# Main.net
KiCad netlist of a schematic drawn in Altium Designer
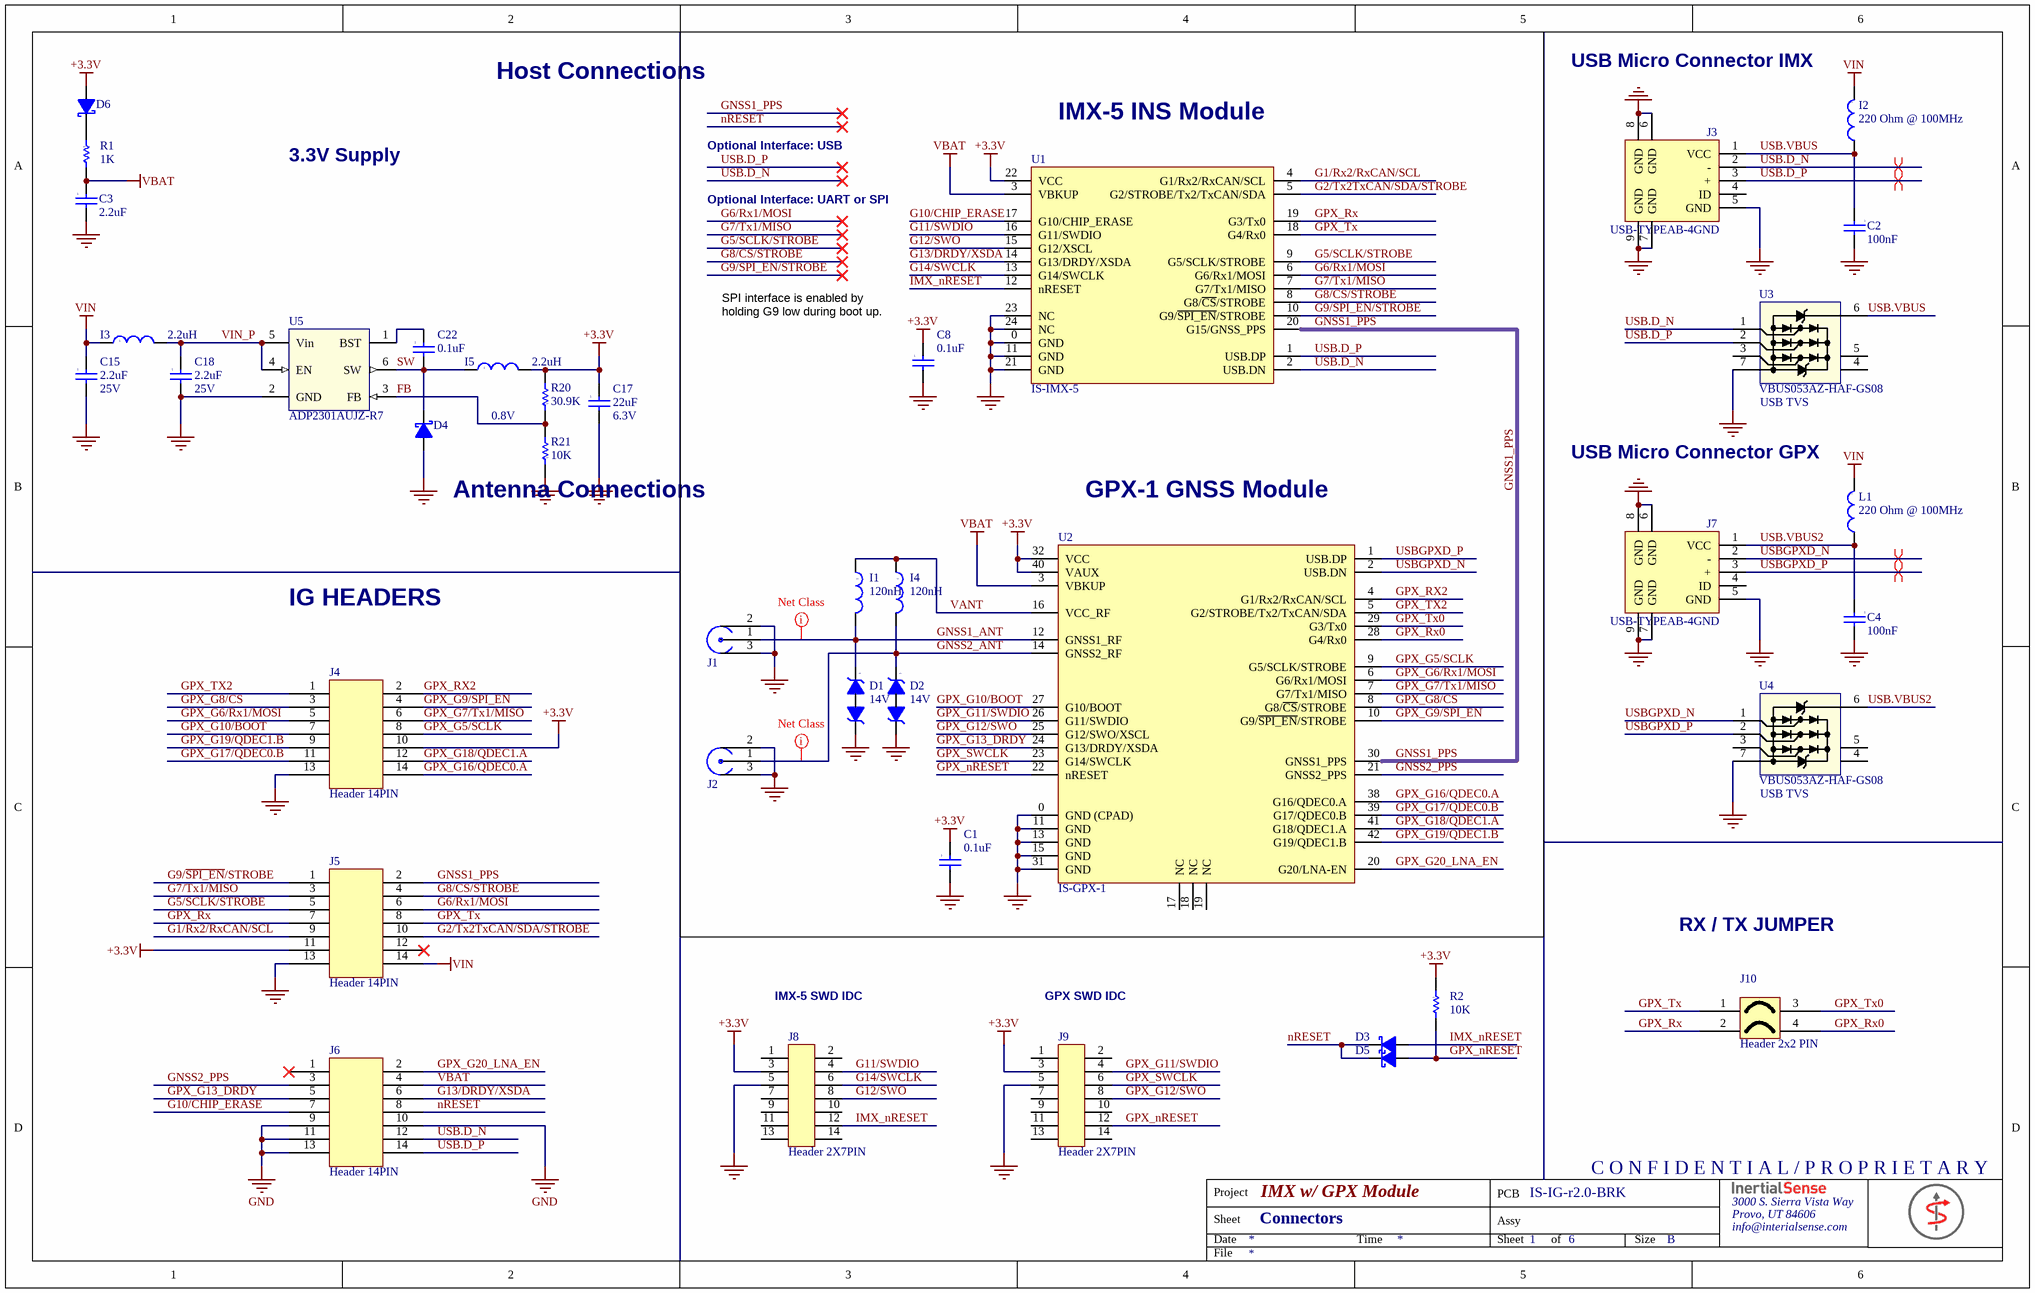
[diagram p0: Main.SchDoc]

(export (version "E")
  (design (tool "Eeschema 10.0.6"))
  (components
    (comp (ref "C1")
      (value "0.1uF")
      (footprint "0402")
      (description "CAP CER .10UF 50V X7R 10% 0402")
      (fields
        (field (name "MANUFACTURER") "TDK Corporation")
        (field (name "MANUFACTURER PART NUMBER") "C1005X7R1H104K")
        (field (name "PUBLISHER") "Altium Limited")
      )
      (libsource (lib "General") (part "Cap"))
    )
    (comp (ref "C2")
      (value "100nF")
      (footprint "0402")
      (description "CAP CER .10UF 50V X7R 10% 0402")
      (fields
        (field (name "MANUFACTURER") "TDK Corporation")
        (field (name "MANUFACTURER PART NUMBER") "C1005X7R1H104K")
        (field (name "PUBLISHER") "Altium Limited")
      )
      (libsource (lib "General") (part "Cap"))
    )
    (comp (ref "C3")
      (value "2.2uF")
      (footprint "0402")
      (description "0402 2.2 uF 6.3 V ±10% Tolerance X6S Multilayer Ceramic Capacitor")
      (fields
        (field (name "MANUFACTURER") "Murata")
        (field (name "MANUFACTURER PART NUMBER") "GRM155C80J225KE95D")
        (field (name "PUBLISHER") "Altium Limited")
      )
      (libsource (lib "General") (part "Cap"))
    )
    (comp (ref "C4")
      (value "100nF")
      (footprint "0402")
      (description "CAP CER .10UF 50V X7R 10% 0402")
      (fields
        (field (name "MANUFACTURER") "TDK Corporation")
        (field (name "MANUFACTURER PART NUMBER") "C1005X7R1H104K")
        (field (name "PUBLISHER") "Altium Limited")
      )
      (libsource (lib "General") (part "Cap"))
    )
    (comp (ref "C8")
      (value "0.1uF")
      (footprint "0402")
      (description "CAP CER .10UF 50V X7R 10% 0402")
      (fields
        (field (name "MANUFACTURER") "TDK Corporation")
        (field (name "MANUFACTURER PART NUMBER") "C1005X7R1H104K")
        (field (name "PUBLISHER") "Altium Limited")
      )
      (libsource (lib "General") (part "Cap"))
    )
    (comp (ref "C15")
      (value "2.2uF")
      (footprint "0603")
      (description "CAP CER 2.2UF 25V X6S 0603")
      (fields
        (field (name "MANUFACTURER") "Murata")
        (field (name "MANUFACTURER PART NUMBER") "GRT188C81E225KE13D")
        (field (name "VOLTAGE RATING") "25V")
        (field (name "PUBLISHER") "Altium Limited")
      )
      (libsource (lib "General") (part "Cap"))
    )
    (comp (ref "C17")
      (value "22uF")
      (footprint "0603")
      (description "CAP CER 22UF 6.3V X6S 0603")
      (fields
        (field (name "MANUFACTURER") "Murata")
        (field (name "MANUFACTURER PART NUMBER") "GRM188C80J226ME15D")
        (field (name "VOLTAGE RATING") "6.3V")
        (field (name "PUBLISHER") "Altium Limited")
      )
      (libsource (lib "General") (part "Cap"))
    )
    (comp (ref "C18")
      (value "2.2uF")
      (footprint "0603")
      (description "CAP CER 2.2UF 25V X6S 0603")
      (fields
        (field (name "MANUFACTURER") "Murata")
        (field (name "MANUFACTURER PART NUMBER") "GRT188C81E225KE13D")
        (field (name "VOLTAGE RATING") "25V")
        (field (name "PUBLISHER") "Altium Limited")
      )
      (libsource (lib "General") (part "Cap"))
    )
    (comp (ref "C22")
      (value "0.1uF")
      (footprint "0402")
      (description "CAP CER 0.1UF 50V X7R 0402")
      (fields
        (field (name "MANUFACTURER") "TDK")
        (field (name "MANUFACTURER PART NUMBER") "CGA2B3X7R1H104K050BB")
        (field (name "PUBLISHER") "Altium Limited")
      )
      (libsource (lib "General") (part "Cap"))
    )
    (comp (ref "D1")
      (value "Diode - Bidirectional Zener")
      (footprint "R0402")
      (description "LITTELFUSE - PESD0402-140 - DIODE, ESD PROTECTION, 0402, FULL REEL")
      (fields
        (field (name "MANUFACTURER") "Littelfuse")
        (field (name "MANUFACTURER PART NUMBER") "PESD0402-140")
        (field (name "WORKING VOLTAGE") "14V")
      )
      (libsource (lib "General") (part "Diode - Bidirectional Zener"))
    )
    (comp (ref "D2")
      (value "Diode - Bidirectional Zener")
      (footprint "R0402")
      (description "LITTELFUSE - PESD0402-140 - DIODE, ESD PROTECTION, 0402, FULL REEL")
      (fields
        (field (name "MANUFACTURER") "Littelfuse")
        (field (name "MANUFACTURER PART NUMBER") "PESD0402-140")
        (field (name "WORKING VOLTAGE") "14V")
      )
      (libsource (lib "General") (part "Diode - Bidirectional Zener"))
    )
    (comp (ref "D3")
      (value "Diode - Schottky")
      (footprint "D0402")
      (description "CDBQR0130L; SMT Schottky Diode; 35V 100mA; 2-Pin SOD-923F (0402)")
      (fields (field (name "MANUFACTURER") "Comchip") (field (name "MANUFACTURER PART NUMBER") "CDBQR0130L"))
      (libsource (lib "General") (part "Diode - Schottky"))
    )
    (comp (ref "D4")
      (value "Diode - Schottky")
      (footprint "D0603B")
      (description "DIODE SCHOTTKY 30V 2A 0603")
      (fields
        (field (name "MANUFACTURER") "Vishay")
        (field (name "MANUFACTURER PART NUMBER") "VSKY20301608-G4-08")
      )
      (libsource (lib "General") (part "Diode - Schottky"))
    )
    (comp (ref "D5")
      (value "Diode - Schottky")
      (footprint "D0402")
      (description "CDBQR0130L; SMT Schottky Diode; 35V 100mA; 2-Pin SOD-923F (0402)")
      (fields (field (name "MANUFACTURER") "Comchip") (field (name "MANUFACTURER PART NUMBER") "CDBQR0130L"))
      (libsource (lib "General") (part "Diode - Schottky"))
    )
    (comp (ref "D6")
      (value "Diode - Schottky")
      (footprint "D0603B")
      (description "DIODE SCHOTTKY 30V 2A 0603")
      (fields
        (field (name "MANUFACTURER") "Vishay")
        (field (name "MANUFACTURER PART NUMBER") "VSKY20301608-G4-08")
      )
      (libsource (lib "General") (part "Diode - Schottky"))
    )
    (comp (ref "I1")
      (value "120nH")
      (footprint "0402")
      (description "Inductor RF Chip Wirewound 120nH 5% 100MHz 20Q-Factor 110mA 2.66Ohm DCR 0402 Paper T/R")
      (fields
        (field (name "MANUFACTURER") "Murata")
        (field (name "MANUFACTURER PART NUMBER") "LQW15ANR12J00D")
      )
      (libsource (lib "General") (part "Inductor"))
    )
    (comp (ref "I2")
      (value "220 Ohm @ 100MHz")
      (footprint "I0603")
      (description "FERRITE CHIP 220 OHM 2500MA 0603")
      (fields
        (field (name "MANUFACTURER") "Murata Electronics North America")
        (field (name "MANUFACTURER PART NUMBER") "BLM18SG221TN1D")
      )
      (libsource (lib "") (part "Inductor_1"))
    )
    (comp (ref "I3")
      (value "2.2uH")
      (footprint "0806")
      (description "FIXED IND 2.2UH 1.2A 110 MOHM")
      (fields
        (field (name "MANUFACTURER") "TDK")
        (field (name "MANUFACTURER PART NUMBER") "MLP2016H2R2MT0S1")
      )
      (libsource (lib "General") (part "Inductor"))
    )
    (comp (ref "I4")
      (value "120nH")
      (footprint "0402")
      (description "Inductor RF Chip Wirewound 120nH 5% 100MHz 20Q-Factor 110mA 2.66Ohm DCR 0402 Paper T/R")
      (fields
        (field (name "MANUFACTURER") "Murata")
        (field (name "MANUFACTURER PART NUMBER") "LQW15ANR12J00D")
      )
      (libsource (lib "General") (part "Inductor"))
    )
    (comp (ref "I5")
      (value "2.2uH")
      (footprint "0806")
      (description "FIXED IND 2.2UH 1.2A 110 MOHM")
      (fields
        (field (name "MANUFACTURER") "TDK")
        (field (name "MANUFACTURER PART NUMBER") "MLP2016H2R2MT0S1")
      )
      (libsource (lib "General") (part "Inductor"))
    )
    (comp (ref "J1")
      (value "RF - GND x 2")
      (footprint "RF UMC SMD")
      (description "CONN UMC RCPT STR 50 OHM SMD")
      (fields
        (field (name "MANUFACTURER") "Emerson Network Power Connectivity Johnson")
        (field (name "MANUFACTURER PART NUMBER") "128-0711-201")
      )
      (libsource (lib "Connectors") (part "RF - GND x 2"))
    )
    (comp (ref "J2")
      (value "RF - GND x 2")
      (footprint "RF UMC SMD")
      (description "CONN UMC RCPT STR 50 OHM SMD")
      (fields
        (field (name "MANUFACTURER") "Emerson Network Power Connectivity Johnson")
        (field (name "MANUFACTURER PART NUMBER") "128-0711-201")
      )
      (libsource (lib "Connectors") (part "RF - GND x 2"))
    )
    (comp (ref "J3")
      (value "USB-TYPEAB-4GND")
      (footprint "USB Micro AB R/A THR")
      (description "CONN USB AB 4POS")
      (fields
        (field (name "MANUFACTURER") "Amphenol FCI")
        (field (name "MANUFACTURER PART NUMBER") "10118194-0001LF")
      )
      (libsource (lib "Connectors") (part "USB-TYPEAB-4GND"))
    )
    (comp (ref "J4")
      (value "Header 14PIN")
      (footprint "Stevelib-2:CONN-HDR2X7V M")
      (description "CONN-HDR2X7B 100MIL T/H")
      (libsource (lib "Stevelib") (part "CONN-HDR2X7B 100MIL T/H"))
    )
    (comp (ref "J5")
      (value "Header 14PIN")
      (footprint "Stevelib-2:CONN-HDR2X7V M")
      (description "CONN-HDR2X7B 100MIL T/H")
      (libsource (lib "Stevelib") (part "CONN-HDR2X7B 100MIL T/H"))
    )
    (comp (ref "J6")
      (value "Header 14PIN")
      (footprint "Stevelib-2:CONN-HDR2X7V M")
      (description "CONN-HDR2X7B 100MIL T/H")
      (libsource (lib "Stevelib") (part "CONN-HDR2X7B 100MIL T/H"))
    )
    (comp (ref "J7")
      (value "USB-TYPEAB-4GND")
      (footprint "USB Micro AB R/A THR")
      (description "CONN USB AB 4POS")
      (fields
        (field (name "MANUFACTURER") "Amphenol FCI")
        (field (name "MANUFACTURER PART NUMBER") "10118194-0001LF")
      )
      (libsource (lib "Connectors") (part "USB-TYPEAB-4GND"))
    )
    (comp (ref "J8")
      (value "Header 2X7PIN")
      (footprint "DT_Lib:CONN-HDR2X7 .050 PITCH")
      (description "CONN-HDR2X7 14P .050MIL T/H")
      (libsource (lib "DT_Lib") (part "CONN-HDR2X7 14P .050MIL T/H"))
    )
    (comp (ref "J9")
      (value "Header 2X7PIN")
      (footprint "DT_Lib:CONN-HDR2X7 .050 PITCH")
      (description "CONN-HDR2X7 14P .050MIL T/H")
      (libsource (lib "DT_Lib") (part "CONN-HDR2X7 14P .050MIL T/H"))
    )
    (comp (ref "J10")
      (value "Header 2x2 PIN")
      (footprint "DT_Lib:CONN-HDR2X2A .100MIL")
      (description "CONN-HDR2X2A 100MIL MALE T/H")
      (fields (field (name "Comment") "CONN-HDR2X2A 100MIL T/H"))
      (libsource (lib "DT_Lib") (part "CONN-HDR2X2A 100MIL T/H"))
    )
    (comp (ref "L1")
      (value "220 Ohm @ 100MHz")
      (footprint "I0603")
      (description "FERRITE CHIP 220 OHM 2500MA 0603")
      (fields
        (field (name "MANUFACTURER") "Murata Electronics North America")
        (field (name "MANUFACTURER PART NUMBER") "BLM18SG221TN1D")
      )
      (libsource (lib "") (part "Inductor_1"))
    )
    (comp (ref "R1")
      (value "1K")
      (footprint "R0402")
      (description "1 kOhms ±1% 0.063W, 1/16W Chip Resistor 0402 (1005 Metric) Moisture Resistant Thick Film")
      (fields
        (field (name "MANUFACTURER") "Yageo")
        (field (name "MANUFACTURER PART NUMBER") "RC0402FR-071KL")
      )
      (libsource (lib "General") (part "Res"))
    )
    (comp (ref "R2")
      (value "10K")
      (footprint "R0402")
      (description "1 kOhms ±1% 0.063W, 1/16W Chip Resistor 0402 (1005 Metric) Moisture Resistant Thick Film")
      (fields
        (field (name "MANUFACTURER") "Stackpole Electronics")
        (field (name "MANUFACTURER PART NUMBER") "RMCF0402FT10K0")
      )
      (libsource (lib "General") (part "Res"))
    )
    (comp (ref "R20")
      (value "30.9K")
      (footprint "R0402")
      (description "RES TF 30.9K OHM 1% 1/16W 0402")
      (fields
        (field (name "MANUFACTURER") "Stackpole Electronics Inc")
        (field (name "MANUFACTURER PART NUMBER") "RMCF0402FT30K9")
      )
      (libsource (lib "General") (part "Res"))
    )
    (comp (ref "R21")
      (value "10K")
      (footprint "R0402")
      (description "RES 10.0K OHM 1/16W 1% 0402 SMD")
      (fields
        (field (name "MANUFACTURER") "Yageo")
        (field (name "MANUFACTURER PART NUMBER") "RC0402FR-0710KL")
      )
      (libsource (lib "General") (part "Res"))
    )
    (comp (ref "U1")
      (value "IMX")
      (footprint "IS-IMX-5.0")
      (description "Inertial Sense IMX")
      (fields
        (field (name "MANUFACTURER") "Inertial Sense")
        (field (name "MANUFACTURER PART NUMBER") "IS-IMX-5")
      )
      (libsource (lib "IS-IMX-5") (part "IS-IMX-5.0"))
    )
    (comp (ref "U2")
      (value "GPX")
      (footprint "IS-GPX-1.0")
      (description "Inertial Sense GPX")
      (fields
        (field (name "MANUFACTURER") "Inertial Sense")
        (field (name "MANUFACTURER PART NUMBER") "IS-GPX-1")
      )
      (libsource (lib "IS-GPX-1") (part "IS-GPX-1.0"))
    )
    (comp (ref "U3")
      (value "VBUS053")
      (footprint "QFN50P160X160X60-6N")
      (description "ESD SUPPRESS 5.5V 36W 3-Line USB")
      (fields
        (field (name "MANUFACTURER") "Vishay Semiconductors")
        (field (name "MANUFACTURER PART NUMBER") "VBUS053AZ-HAF-GS08")
      )
      (libsource (lib "ICs") (part "VBUS053"))
    )
    (comp (ref "U4")
      (value "VBUS053")
      (footprint "QFN50P160X160X60-6N")
      (description "ESD SUPPRESS 5.5V 36W 3-Line USB")
      (fields
        (field (name "MANUFACTURER") "Vishay Semiconductors")
        (field (name "MANUFACTURER PART NUMBER") "VBUS053AZ-HAF-GS08")
      )
      (libsource (lib "ICs") (part "VBUS053"))
    )
    (comp (ref "U5")
      (value "ADP2301")
      (footprint "MO-178-AB")
      (description "IC BUCK ADJ 1.2A 6TSOT")
      (fields
        (field (name "MANUFACTURER") "Analog Devices Inc")
        (field (name "MANUFACTURER PART NUMBER") "ADP2301AUJZ-R7")
      )
      (libsource (lib "ICs") (part "ADP2301"))
    )
  )
  (nets
    (net (code "1") (name "+3.3V") (class "Default")
      (node (ref "C1") (pin "1") (pinfunction "1_1") (pintype "passive"))
      (node (ref "C17") (pin "1") (pinfunction "1_1") (pintype "passive"))
      (node (ref "C8") (pin "1") (pinfunction "1_1") (pintype "passive"))
      (node (ref "D6") (pin "A") (pinfunction "A_A") (pintype "passive"))
      (node (ref "I5") (pin "2") (pinfunction "2_2") (pintype "passive"))
      (node (ref "J4") (pin "10") (pinfunction "10_10") (pintype "passive"))
      (node (ref "J5") (pin "11") (pinfunction "11_11") (pintype "passive"))
      (node (ref "J8") (pin "3") (pinfunction "3_3") (pintype "passive"))
      (node (ref "J9") (pin "3") (pinfunction "3_3") (pintype "passive"))
      (node (ref "R2") (pin "1") (pinfunction "1_1") (pintype "passive"))
      (node (ref "R20") (pin "2") (pinfunction "2_2") (pintype "passive"))
      (node (ref "U1") (pin "22") (pinfunction "VCC_22") (pintype "power_in"))
      (node (ref "U2") (pin "32") (pinfunction "VCC_32") (pintype "power_in"))
      (node (ref "U2") (pin "40") (pinfunction "VAUX_40") (pintype "power_in"))
    )
    (net (code "2") (name "/FB") (class "Default")
      (node (ref "R20") (pin "1") (pinfunction "1_1") (pintype "passive"))
      (node (ref "R21") (pin "2") (pinfunction "2_2") (pintype "passive"))
      (node (ref "U5") (pin "3") (pinfunction "FB_3") (pintype "input"))
    )
    (net (code "3") (name "/G1{slash}Rx2{slash}RxCAN{slash}SCL") (class "Default")
      (node (ref "J5") (pin "9") (pinfunction "9_9") (pintype "passive"))
      (node (ref "U1") (pin "4") (pinfunction "G1/Rx2/RxCAN/SCL_4") (pintype "passive"))
    )
    (net (code "4") (name "/G2{slash}Tx2TxCAN{slash}SDA{slash}STROBE") (class "Default")
      (node (ref "J5") (pin "10") (pinfunction "10_10") (pintype "passive"))
      (node (ref "U1") (pin "5") (pinfunction "G2/STROBE/Tx2/TxCAN/SDA_5") (pintype "passive"))
    )
    (net (code "5") (name "/G5{slash}SCLK{slash}STROBE") (class "Default")
      (node (ref "J5") (pin "5") (pinfunction "5_5") (pintype "passive"))
      (node (ref "U1") (pin "9") (pinfunction "G5/SCLK/STROBE_9") (pintype "passive"))
    )
    (net (code "6") (name "/G6{slash}Rx1{slash}MOSI") (class "Default")
      (node (ref "J5") (pin "6") (pinfunction "6_6") (pintype "passive"))
      (node (ref "U1") (pin "6") (pinfunction "G6/Rx1/MOSI_6") (pintype "passive"))
    )
    (net (code "7") (name "/G7{slash}Tx1{slash}MISO") (class "Default")
      (node (ref "J5") (pin "3") (pinfunction "3_3") (pintype "passive"))
      (node (ref "U1") (pin "7") (pinfunction "G7/Tx1/MISO_7") (pintype "passive"))
    )
    (net (code "8") (name "/G8{slash}~{CS}{slash}STROBE") (class "Default")
      (node (ref "J5") (pin "4") (pinfunction "4_4") (pintype "passive"))
      (node (ref "U1") (pin "8") (pinfunction "G8/~{CS}/STROBE_8") (pintype "passive"))
    )
    (net (code "9") (name "/G9{slash}~{SPI_EN}{slash}STROBE") (class "Default")
      (node (ref "J5") (pin "1") (pinfunction "1_1") (pintype "passive"))
      (node (ref "U1") (pin "10") (pinfunction "G9/~{SPI_EN}/STROBE_10") (pintype "passive"))
    )
    (net (code "10") (name "/G10{slash}CHIP_ERASE") (class "Default")
      (node (ref "J6") (pin "7") (pinfunction "7_7") (pintype "passive"))
      (node (ref "U1") (pin "17") (pinfunction "G10/CHIP_ERASE_17") (pintype "passive"))
    )
    (net (code "11") (name "/G11{slash}SWDIO") (class "Default")
      (node (ref "J8") (pin "4") (pinfunction "4_4") (pintype "passive"))
      (node (ref "U1") (pin "16") (pinfunction "G11/SWDIO_16") (pintype "passive"))
    )
    (net (code "12") (name "/G12{slash}SWO") (class "Default")
      (node (ref "J8") (pin "8") (pinfunction "8_8") (pintype "passive"))
      (node (ref "U1") (pin "15") (pinfunction "G12/XSCL_15") (pintype "passive"))
    )
    (net (code "13") (name "/G13{slash}DRDY{slash}XSDA") (class "Default")
      (node (ref "J6") (pin "6") (pinfunction "6_6") (pintype "passive"))
      (node (ref "U1") (pin "14") (pinfunction "G13/DRDY/XSDA_14") (pintype "passive"))
    )
    (net (code "14") (name "/G14{slash}SWCLK") (class "Default")
      (node (ref "J8") (pin "6") (pinfunction "6_6") (pintype "passive"))
      (node (ref "U1") (pin "13") (pinfunction "G14/SWCLK_13") (pintype "passive"))
    )
    (net (code "15") (name "/GNSS1_ANT") (class "Default")
      (node (ref "D1") (pin "1") (pinfunction "1_1") (pintype "passive"))
      (node (ref "I1") (pin "2") (pinfunction "2_2") (pintype "passive"))
      (node (ref "J1") (pin "1") (pinfunction "1_1") (pintype "passive"))
      (node (ref "U2") (pin "12") (pinfunction "GNSS1_RF_12") (pintype "passive"))
    )
    (net (code "16") (name "/GNSS1_PPS") (class "Default")
      (node (ref "J5") (pin "2") (pinfunction "2_2") (pintype "passive"))
      (node (ref "U1") (pin "20") (pinfunction "G15/GNSS_PPS_20") (pintype "passive"))
      (node (ref "U2") (pin "30") (pinfunction "GNSS1_PPS_30") (pintype "passive"))
    )
    (net (code "17") (name "/GNSS2_ANT") (class "Default")
      (node (ref "D2") (pin "1") (pinfunction "1_1") (pintype "passive"))
      (node (ref "I4") (pin "2") (pinfunction "2_2") (pintype "passive"))
      (node (ref "J2") (pin "1") (pinfunction "1_1") (pintype "passive"))
      (node (ref "U2") (pin "14") (pinfunction "GNSS2_RF_14") (pintype "passive"))
    )
    (net (code "18") (name "/GNSS2_PPS") (class "Default")
      (node (ref "J6") (pin "3") (pinfunction "3_3") (pintype "passive"))
      (node (ref "U2") (pin "21") (pinfunction "GNSS2_PPS_21") (pintype "passive"))
    )
    (net (code "19") (name "/GPX_G5{slash}SCLK") (class "Default")
      (node (ref "J4") (pin "8") (pinfunction "8_8") (pintype "passive"))
      (node (ref "U2") (pin "9") (pinfunction "G5/SCLK/STROBE_9") (pintype "passive"))
    )
    (net (code "20") (name "/GPX_G6{slash}Rx1{slash}MOSI") (class "Default")
      (node (ref "J4") (pin "5") (pinfunction "5_5") (pintype "passive"))
      (node (ref "U2") (pin "6") (pinfunction "G6/Rx1/MOSI_6") (pintype "passive"))
    )
    (net (code "21") (name "/GPX_G7{slash}Tx1{slash}MISO") (class "Default")
      (node (ref "J4") (pin "6") (pinfunction "6_6") (pintype "passive"))
      (node (ref "U2") (pin "7") (pinfunction "G7/Tx1/MISO_7") (pintype "passive"))
    )
    (net (code "22") (name "/GPX_G8{slash}~{CS}") (class "Default")
      (node (ref "J4") (pin "3") (pinfunction "3_3") (pintype "passive"))
      (node (ref "U2") (pin "8") (pinfunction "G8/~{CS}/STROBE_8") (pintype "passive"))
    )
    (net (code "23") (name "/GPX_G9{slash}~{SPI_EN}") (class "Default")
      (node (ref "J4") (pin "4") (pinfunction "4_4") (pintype "passive"))
      (node (ref "U2") (pin "10") (pinfunction "G9/~{SPI_EN}/STROBE_10") (pintype "passive"))
    )
    (net (code "24") (name "/GPX_G10{slash}BOOT") (class "Default")
      (node (ref "J4") (pin "7") (pinfunction "7_7") (pintype "passive"))
      (node (ref "U2") (pin "27") (pinfunction "G10/BOOT_27") (pintype "passive"))
    )
    (net (code "25") (name "/GPX_G11{slash}SWDIO") (class "Default")
      (node (ref "J9") (pin "4") (pinfunction "4_4") (pintype "passive"))
      (node (ref "U2") (pin "26") (pinfunction "G11/SWDIO_26") (pintype "passive"))
    )
    (net (code "26") (name "/GPX_G12{slash}SWO") (class "Default")
      (node (ref "J9") (pin "8") (pinfunction "8_8") (pintype "passive"))
      (node (ref "U2") (pin "25") (pinfunction "G12/SWO/XSCL_25") (pintype "passive"))
    )
    (net (code "27") (name "/GPX_G13_DRDY") (class "Default")
      (node (ref "J6") (pin "5") (pinfunction "5_5") (pintype "passive"))
      (node (ref "U2") (pin "24") (pinfunction "G13/DRDY/XSDA_24") (pintype "passive"))
    )
    (net (code "28") (name "/GPX_G16{slash}QDEC0.A") (class "Default")
      (node (ref "J4") (pin "14") (pinfunction "14_14") (pintype "passive"))
      (node (ref "U2") (pin "38") (pinfunction "G16/QDEC0.A_38") (pintype "passive"))
    )
    (net (code "29") (name "/GPX_G17{slash}QDEC0.B") (class "Default")
      (node (ref "J4") (pin "11") (pinfunction "11_11") (pintype "passive"))
      (node (ref "U2") (pin "39") (pinfunction "G17/QDEC0.B_39") (pintype "passive"))
    )
    (net (code "30") (name "/GPX_G18{slash}QDEC1.A") (class "Default")
      (node (ref "J4") (pin "12") (pinfunction "12_12") (pintype "passive"))
      (node (ref "U2") (pin "41") (pinfunction "G18/QDEC1.A_41") (pintype "passive"))
    )
    (net (code "31") (name "/GPX_G19{slash}QDEC1.B") (class "Default")
      (node (ref "J4") (pin "9") (pinfunction "9_9") (pintype "passive"))
      (node (ref "U2") (pin "42") (pinfunction "G19/QDEC1.B_42") (pintype "passive"))
    )
    (net (code "32") (name "/GPX_G20_LNA_EN") (class "Default")
      (node (ref "J6") (pin "2") (pinfunction "2_2") (pintype "passive"))
      (node (ref "U2") (pin "20") (pinfunction "G20/LNA-EN_20") (pintype "passive"))
    )
    (net (code "33") (name "/GPX_RX2") (class "Default")
      (node (ref "J4") (pin "2") (pinfunction "2_2") (pintype "passive"))
      (node (ref "U2") (pin "4") (pinfunction "G1/Rx2/RxCAN/SCL_4") (pintype "passive"))
    )
    (net (code "34") (name "/GPX_Rx") (class "Default")
      (node (ref "J10") (pin "2") (pinfunction "2_2") (pintype "passive"))
      (node (ref "J5") (pin "7") (pinfunction "7_7") (pintype "passive"))
      (node (ref "U1") (pin "19") (pinfunction "G3/Tx0_19") (pintype "passive"))
    )
    (net (code "35") (name "/GPX_Rx0") (class "Default")
      (node (ref "J10") (pin "4") (pinfunction "4_4") (pintype "passive"))
      (node (ref "U2") (pin "28") (pinfunction "G4/Rx0_28") (pintype "passive"))
    )
    (net (code "36") (name "/GPX_SWCLK") (class "Default")
      (node (ref "J9") (pin "6") (pinfunction "6_6") (pintype "passive"))
      (node (ref "U2") (pin "23") (pinfunction "G14/SWCLK_23") (pintype "passive"))
    )
    (net (code "37") (name "/GPX_TX2") (class "Default")
      (node (ref "J4") (pin "1") (pinfunction "1_1") (pintype "passive"))
      (node (ref "U2") (pin "5") (pinfunction "G2/STROBE/Tx2/TxCAN/SDA_5") (pintype "passive"))
    )
    (net (code "38") (name "/GPX_Tx") (class "Default")
      (node (ref "J10") (pin "1") (pinfunction "1_1") (pintype "passive"))
      (node (ref "J5") (pin "8") (pinfunction "8_8") (pintype "passive"))
      (node (ref "U1") (pin "18") (pinfunction "G4/Rx0_18") (pintype "passive"))
    )
    (net (code "39") (name "/GPX_Tx0") (class "Default")
      (node (ref "J10") (pin "3") (pinfunction "3_3") (pintype "passive"))
      (node (ref "U2") (pin "29") (pinfunction "G3/Tx0_29") (pintype "passive"))
    )
    (net (code "40") (name "/GPX_nRESET") (class "Default")
      (node (ref "D5") (pin "A") (pinfunction "A_A") (pintype "passive"))
      (node (ref "J9") (pin "12") (pinfunction "12_12") (pintype "passive"))
      (node (ref "R2") (pin "2") (pinfunction "2_2") (pintype "passive"))
      (node (ref "U2") (pin "22") (pinfunction "nRESET_22") (pintype "passive"))
    )
    (net (code "41") (name "/IMX_nRESET") (class "Default")
      (node (ref "D3") (pin "A") (pinfunction "A_A") (pintype "passive"))
      (node (ref "J8") (pin "12") (pinfunction "12_12") (pintype "passive"))
      (node (ref "U1") (pin "12") (pinfunction "nRESET_12") (pintype "passive"))
    )
    (net (code "42") (name "/SW") (class "Default")
      (node (ref "C22") (pin "2") (pinfunction "2_2") (pintype "passive"))
      (node (ref "D4") (pin "C") (pinfunction "C_C") (pintype "passive"))
      (node (ref "I5") (pin "1") (pinfunction "1_1") (pintype "passive"))
      (node (ref "U5") (pin "6") (pinfunction "SW_6") (pintype "output"))
    )
    (net (code "43") (name "/USB.D_N") (class "Default")
      (node (ref "J3") (pin "2") (pinfunction "-_2") (pintype "passive"))
      (node (ref "J6") (pin "12") (pinfunction "12_12") (pintype "passive"))
      (node (ref "U1") (pin "2") (pinfunction "USB.DN_2") (pintype "passive"))
      (node (ref "U3") (pin "1") (pintype "passive"))
    )
    (net (code "44") (name "/USB.D_P") (class "Default")
      (node (ref "J3") (pin "3") (pinfunction "+_3") (pintype "passive"))
      (node (ref "J6") (pin "14") (pinfunction "14_14") (pintype "passive"))
      (node (ref "U1") (pin "1") (pinfunction "USB.DP_1") (pintype "passive"))
      (node (ref "U3") (pin "2") (pintype "passive"))
    )
    (net (code "45") (name "/USB.VBUS") (class "Default")
      (node (ref "C2") (pin "1") (pinfunction "1_1") (pintype "passive"))
      (node (ref "I2") (pin "2") (pinfunction "2_2") (pintype "passive"))
      (node (ref "J3") (pin "1") (pinfunction "VCC_1") (pintype "passive"))
      (node (ref "U3") (pin "6") (pintype "passive"))
    )
    (net (code "46") (name "/USB.VBUS2") (class "Default")
      (node (ref "C4") (pin "1") (pinfunction "1_1") (pintype "passive"))
      (node (ref "J7") (pin "1") (pinfunction "VCC_1") (pintype "passive"))
      (node (ref "L1") (pin "2") (pinfunction "2_2") (pintype "passive"))
      (node (ref "U4") (pin "6") (pintype "passive"))
    )
    (net (code "47") (name "/USBGPXD_N") (class "Default")
      (node (ref "J7") (pin "2") (pinfunction "-_2") (pintype "passive"))
      (node (ref "U2") (pin "2") (pinfunction "USB.DN_2") (pintype "passive"))
      (node (ref "U4") (pin "1") (pintype "passive"))
    )
    (net (code "48") (name "/USBGPXD_P") (class "Default")
      (node (ref "J7") (pin "3") (pinfunction "+_3") (pintype "passive"))
      (node (ref "U2") (pin "1") (pinfunction "USB.DP_1") (pintype "passive"))
      (node (ref "U4") (pin "2") (pintype "passive"))
    )
    (net (code "49") (name "/VANT") (class "Default")
      (node (ref "I1") (pin "1") (pinfunction "1_1") (pintype "passive"))
      (node (ref "I4") (pin "1") (pinfunction "1_1") (pintype "passive"))
      (node (ref "U2") (pin "16") (pinfunction "VCC_RF_16") (pintype "power_in"))
    )
    (net (code "50") (name "/VIN_P") (class "Default")
      (node (ref "C18") (pin "1") (pinfunction "1_1") (pintype "passive"))
      (node (ref "I3") (pin "2") (pinfunction "2_2") (pintype "passive"))
      (node (ref "U5") (pin "4") (pinfunction "EN_4") (pintype "input"))
      (node (ref "U5") (pin "5") (pinfunction "Vin_5") (pintype "power_in"))
    )
    (net (code "51") (name "/nRESET") (class "Default")
      (node (ref "D3") (pin "C") (pinfunction "C_C") (pintype "passive"))
      (node (ref "D5") (pin "C") (pinfunction "C_C") (pintype "passive"))
      (node (ref "J6") (pin "8") (pinfunction "8_8") (pintype "passive"))
    )
    (net (code "52") (name "GND") (class "Default")
      (node (ref "C1") (pin "2") (pinfunction "2_2") (pintype "passive"))
      (node (ref "C15") (pin "2") (pinfunction "2_2") (pintype "passive"))
      (node (ref "C17") (pin "2") (pinfunction "2_2") (pintype "passive"))
      (node (ref "C18") (pin "2") (pinfunction "2_2") (pintype "passive"))
      (node (ref "C2") (pin "2") (pinfunction "2_2") (pintype "passive"))
      (node (ref "C3") (pin "2") (pinfunction "2_2") (pintype "passive"))
      (node (ref "C4") (pin "2") (pinfunction "2_2") (pintype "passive"))
      (node (ref "C8") (pin "2") (pinfunction "2_2") (pintype "passive"))
      (node (ref "D1") (pin "2") (pinfunction "2_2") (pintype "passive"))
      (node (ref "D2") (pin "2") (pinfunction "2_2") (pintype "passive"))
      (node (ref "D4") (pin "A") (pinfunction "A_A") (pintype "passive"))
      (node (ref "J1") (pin "2") (pinfunction "2_2") (pintype "passive"))
      (node (ref "J1") (pin "3") (pinfunction "3_3") (pintype "passive"))
      (node (ref "J2") (pin "2") (pinfunction "2_2") (pintype "passive"))
      (node (ref "J2") (pin "3") (pinfunction "3_3") (pintype "passive"))
      (node (ref "J3") (pin "5") (pinfunction "GND_5") (pintype "passive"))
      (node (ref "J3") (pin "6") (pinfunction "GND_6") (pintype "passive"))
      (node (ref "J3") (pin "7") (pinfunction "GND_7") (pintype "passive"))
      (node (ref "J3") (pin "8") (pinfunction "GND_8") (pintype "passive"))
      (node (ref "J3") (pin "9") (pinfunction "GND_9") (pintype "passive"))
      (node (ref "J4") (pin "13") (pinfunction "13_13") (pintype "passive"))
      (node (ref "J5") (pin "13") (pinfunction "13_13") (pintype "passive"))
      (node (ref "J6") (pin "10") (pinfunction "10_10") (pintype "passive"))
      (node (ref "J6") (pin "11") (pinfunction "11_11") (pintype "passive"))
      (node (ref "J6") (pin "13") (pinfunction "13_13") (pintype "passive"))
      (node (ref "J6") (pin "9") (pinfunction "9_9") (pintype "passive"))
      (node (ref "J7") (pin "5") (pinfunction "GND_5") (pintype "passive"))
      (node (ref "J7") (pin "6") (pinfunction "GND_6") (pintype "passive"))
      (node (ref "J7") (pin "7") (pinfunction "GND_7") (pintype "passive"))
      (node (ref "J7") (pin "8") (pinfunction "GND_8") (pintype "passive"))
      (node (ref "J7") (pin "9") (pinfunction "GND_9") (pintype "passive"))
      (node (ref "J8") (pin "5") (pinfunction "5_5") (pintype "passive"))
      (node (ref "J9") (pin "5") (pinfunction "5_5") (pintype "passive"))
      (node (ref "R21") (pin "1") (pinfunction "1_1") (pintype "passive"))
      (node (ref "U1") (pin "0") (pinfunction "GND_0") (pintype "power_in"))
      (node (ref "U1") (pin "11") (pinfunction "GND_11") (pintype "power_in"))
      (node (ref "U1") (pin "21") (pinfunction "GND_21") (pintype "power_in"))
      (node (ref "U1") (pin "23") (pinfunction "NC_23") (pintype "power_in"))
      (node (ref "U1") (pin "24") (pinfunction "NC_24") (pintype "power_in"))
      (node (ref "U2") (pin "0") (pinfunction "GND_(CPAD)_0") (pintype "power_in"))
      (node (ref "U2") (pin "11") (pinfunction "GND_11") (pintype "power_in"))
      (node (ref "U2") (pin "13") (pinfunction "GND_13") (pintype "power_in"))
      (node (ref "U2") (pin "15") (pinfunction "GND_15") (pintype "power_in"))
      (node (ref "U2") (pin "31") (pinfunction "GND_31") (pintype "power_in"))
      (node (ref "U3") (pin "7") (pintype "passive"))
      (node (ref "U4") (pin "7") (pintype "passive"))
      (node (ref "U5") (pin "2") (pinfunction "GND_2") (pintype "power_in"))
    )
    (net (code "53") (name "Net-(D6-PadC)") (class "Default")
      (node (ref "D6") (pin "C") (pinfunction "C_C") (pintype "passive"))
      (node (ref "R1") (pin "1") (pinfunction "1_1") (pintype "passive"))
    )
    (net (code "54") (name "Net-(U5-BST)") (class "Default")
      (node (ref "C22") (pin "1") (pinfunction "1_1") (pintype "passive"))
      (node (ref "U5") (pin "1") (pinfunction "BST_1") (pintype "passive"))
    )
    (net (code "55") (name "VBAT") (class "Default")
      (node (ref "C3") (pin "1") (pinfunction "1_1") (pintype "passive"))
      (node (ref "J6") (pin "4") (pinfunction "4_4") (pintype "passive"))
      (node (ref "R1") (pin "2") (pinfunction "2_2") (pintype "passive"))
      (node (ref "U1") (pin "3") (pinfunction "VBKUP_3") (pintype "passive"))
      (node (ref "U2") (pin "3") (pinfunction "VBKUP_3") (pintype "passive"))
    )
    (net (code "56") (name "VIN") (class "Default")
      (node (ref "C15") (pin "1") (pinfunction "1_1") (pintype "passive"))
      (node (ref "I2") (pin "1") (pinfunction "1_1") (pintype "passive"))
      (node (ref "I3") (pin "1") (pinfunction "1_1") (pintype "passive"))
      (node (ref "J5") (pin "14") (pinfunction "14_14") (pintype "passive"))
      (node (ref "L1") (pin "1") (pinfunction "1_1") (pintype "passive"))
    )
    (net (code "57") (name "unconnected-(J3-ID-Pad4)") (class "Default")
      (node (ref "J3") (pin "4") (pinfunction "ID_4") (pintype "passive"))
    )
    (net (code "58") (name "unconnected-(J5-Pad12)") (class "Default")
      (node (ref "J5") (pin "12") (pinfunction "12_12") (pintype "passive+no_connect"))
    )
    (net (code "59") (name "unconnected-(J6-Pad1)") (class "Default")
      (node (ref "J6") (pin "1") (pinfunction "1_1") (pintype "passive+no_connect"))
    )
    (net (code "60") (name "unconnected-(J7-ID-Pad4)") (class "Default")
      (node (ref "J7") (pin "4") (pinfunction "ID_4") (pintype "passive"))
    )
    (net (code "61") (name "unconnected-(J8-Pad1)") (class "Default")
      (node (ref "J8") (pin "1") (pinfunction "1_1") (pintype "passive"))
    )
    (net (code "62") (name "unconnected-(J8-Pad2)") (class "Default")
      (node (ref "J8") (pin "2") (pinfunction "2_2") (pintype "passive"))
    )
    (net (code "63") (name "unconnected-(J8-Pad7)") (class "Default")
      (node (ref "J8") (pin "7") (pinfunction "7_7") (pintype "passive"))
    )
    (net (code "64") (name "unconnected-(J8-Pad9)") (class "Default")
      (node (ref "J8") (pin "9") (pinfunction "9_9") (pintype "passive"))
    )
    (net (code "65") (name "unconnected-(J8-Pad10)") (class "Default")
      (node (ref "J8") (pin "10") (pinfunction "10_10") (pintype "passive"))
    )
    (net (code "66") (name "unconnected-(J8-Pad11)") (class "Default")
      (node (ref "J8") (pin "11") (pinfunction "11_11") (pintype "passive"))
    )
    (net (code "67") (name "unconnected-(J8-Pad13)") (class "Default")
      (node (ref "J8") (pin "13") (pinfunction "13_13") (pintype "passive"))
    )
    (net (code "68") (name "unconnected-(J8-Pad14)") (class "Default")
      (node (ref "J8") (pin "14") (pinfunction "14_14") (pintype "passive"))
    )
    (net (code "69") (name "unconnected-(J9-Pad1)") (class "Default")
      (node (ref "J9") (pin "1") (pinfunction "1_1") (pintype "passive"))
    )
    (net (code "70") (name "unconnected-(J9-Pad2)") (class "Default")
      (node (ref "J9") (pin "2") (pinfunction "2_2") (pintype "passive"))
    )
    (net (code "71") (name "unconnected-(J9-Pad7)") (class "Default")
      (node (ref "J9") (pin "7") (pinfunction "7_7") (pintype "passive"))
    )
    (net (code "72") (name "unconnected-(J9-Pad9)") (class "Default")
      (node (ref "J9") (pin "9") (pinfunction "9_9") (pintype "passive"))
    )
    (net (code "73") (name "unconnected-(J9-Pad10)") (class "Default")
      (node (ref "J9") (pin "10") (pinfunction "10_10") (pintype "passive"))
    )
    (net (code "74") (name "unconnected-(J9-Pad11)") (class "Default")
      (node (ref "J9") (pin "11") (pinfunction "11_11") (pintype "passive"))
    )
    (net (code "75") (name "unconnected-(J9-Pad13)") (class "Default")
      (node (ref "J9") (pin "13") (pinfunction "13_13") (pintype "passive"))
    )
    (net (code "76") (name "unconnected-(J9-Pad14)") (class "Default")
      (node (ref "J9") (pin "14") (pinfunction "14_14") (pintype "passive"))
    )
    (net (code "77") (name "unconnected-(U2-NC-Pad17)") (class "Default")
      (node (ref "U2") (pin "17") (pinfunction "NC_17") (pintype "passive"))
    )
    (net (code "78") (name "unconnected-(U2-NC-Pad18)") (class "Default")
      (node (ref "U2") (pin "18") (pinfunction "NC_18") (pintype "passive"))
    )
    (net (code "79") (name "unconnected-(U2-NC-Pad19)") (class "Default")
      (node (ref "U2") (pin "19") (pinfunction "NC_19") (pintype "passive"))
    )
    (net (code "80") (name "unconnected-(U3-Pad3)") (class "Default")
      (node (ref "U3") (pin "3") (pintype "passive"))
    )
    (net (code "81") (name "unconnected-(U3-nc-Pad4)") (class "Default")
      (node (ref "U3") (pin "4") (pinfunction "nc_4") (pintype "passive"))
    )
    (net (code "82") (name "unconnected-(U3-nc-Pad5)") (class "Default")
      (node (ref "U3") (pin "5") (pinfunction "nc_5") (pintype "passive"))
    )
    (net (code "83") (name "unconnected-(U4-Pad3)") (class "Default")
      (node (ref "U4") (pin "3") (pintype "passive"))
    )
    (net (code "84") (name "unconnected-(U4-nc-Pad4)") (class "Default")
      (node (ref "U4") (pin "4") (pinfunction "nc_4") (pintype "passive"))
    )
    (net (code "85") (name "unconnected-(U4-nc-Pad5)") (class "Default")
      (node (ref "U4") (pin "5") (pinfunction "nc_5") (pintype "passive"))
    )
  )
)
